# ESP8266.net
KiCad netlist of a schematic drawn in EasyEDA Pro
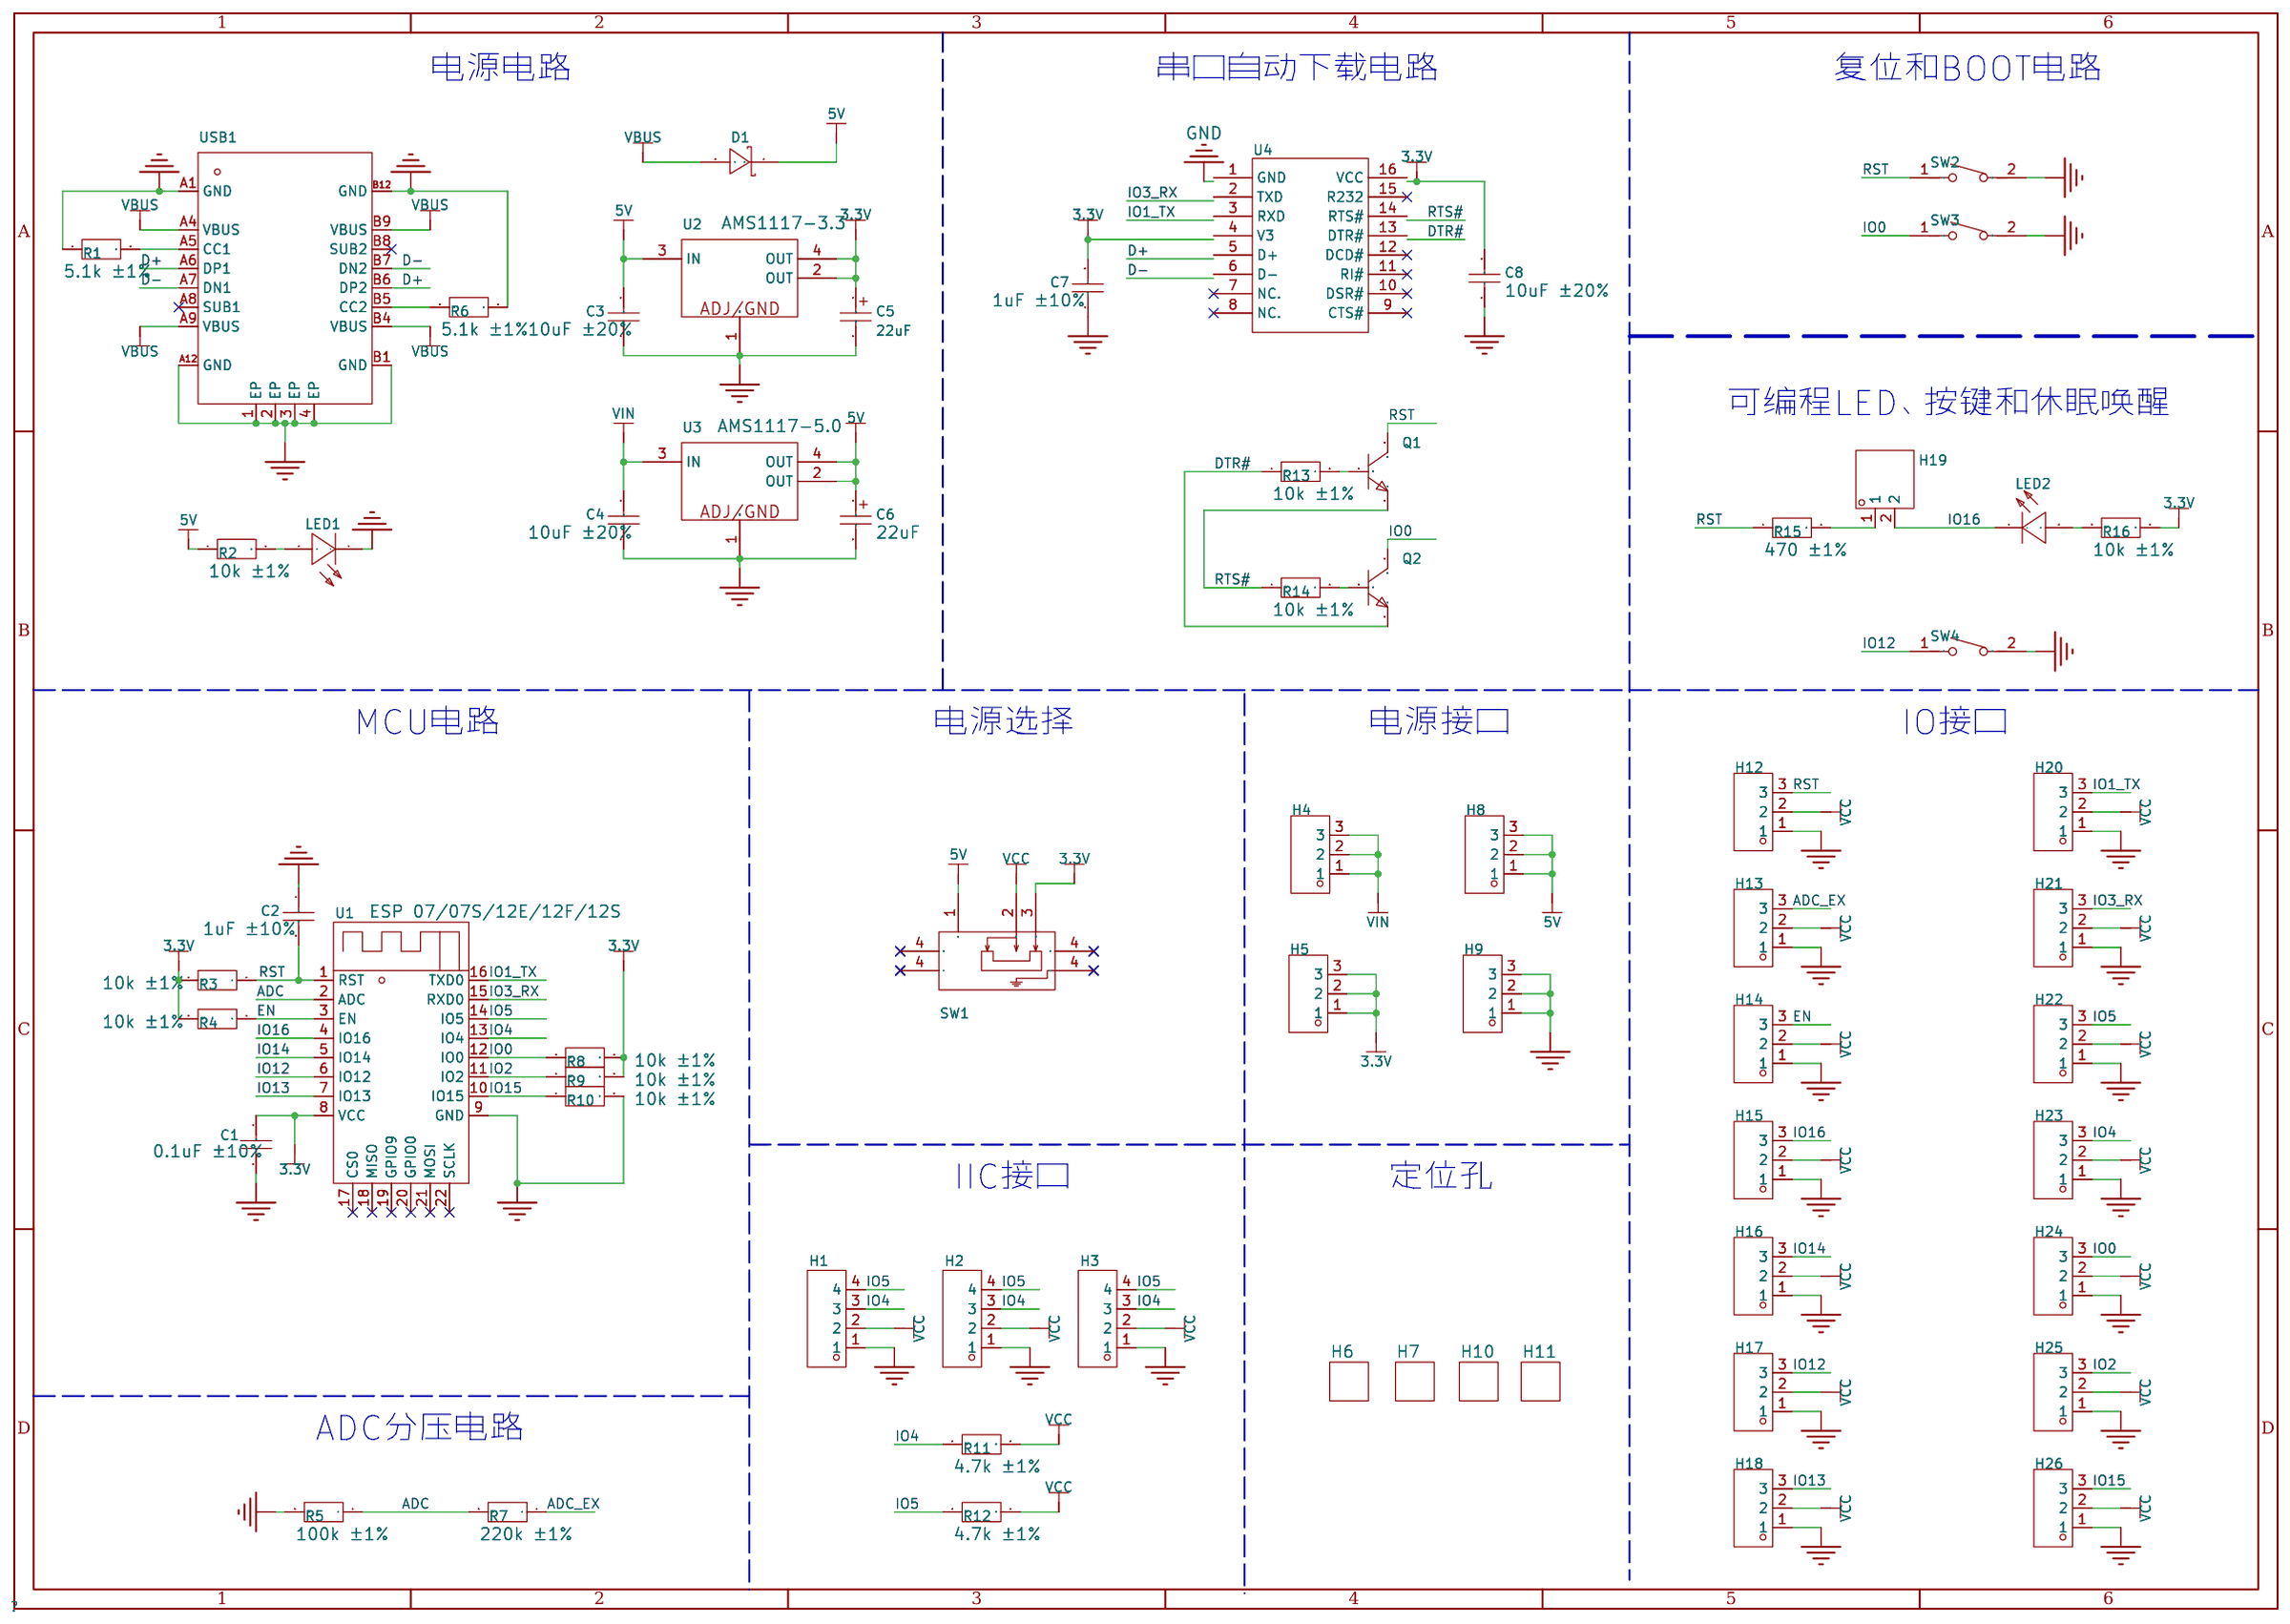
[diagram p0: schematic sheet]

(export (version "E")
  (design (tool "Eeschema 10.0.6"))
  (components
    (comp (ref "C1")
      (value "0.1uF ±10%")
      (footprint "easyedapro:C0603")
      (description "1uF ±10%")
      (libsource (lib "easyedapro") (part "C0603"))
    )
    (comp (ref "C2")
      (value "1uF ±10%")
      (footprint "easyedapro:C0603")
      (libsource (lib "easyedapro") (part "C0603"))
    )
    (comp (ref "C3")
      (value "10uF ±20%")
      (footprint "easyedapro:C0603")
      (description "10uF ±10%")
      (libsource (lib "easyedapro") (part "C0603"))
    )
    (comp (ref "C4")
      (value "10uF ±20%")
      (footprint "easyedapro:C0603")
      (description "10uF ±10%")
      (libsource (lib "easyedapro") (part "C0603"))
    )
    (comp (ref "C5")
      (value "22uF")
      (footprint "easyedapro:CAP-SMD_L3.5-W2.8-R-RD")
      (fields
        (field (name "Manufacturer Part") "CA45-B-25V-22uF-K")
        (field (name "Manufacturer") "CEC(振华新云)")
      )
      (libsource (lib "easyedapro") (part "CA45-B-25V-22UF"))
    )
    (comp (ref "C6")
      (value "22uF")
      (footprint "easyedapro:CAP-SMD_L3.5-W2.8-R-RD")
      (fields
        (field (name "Manufacturer Part") "CA45-B-25V-22uF-K")
        (field (name "Manufacturer") "CEC(振华新云)")
      )
      (libsource (lib "easyedapro") (part "CA45-B-25V-22UF"))
    )
    (comp (ref "C7")
      (value "1uF ±10%")
      (footprint "easyedapro:C0603")
      (libsource (lib "easyedapro") (part "C0603"))
    )
    (comp (ref "C8")
      (value "10uF ±20%")
      (footprint "easyedapro:C0603")
      (libsource (lib "easyedapro") (part "C0603"))
    )
    (comp (ref "D1")
      (value "SS24")
      (footprint "easyedapro:DO-214AC_L4.3-W2.7-LS5.3-RD")
      (description "直流反向耐压(Vr):40V;平均整流电流(Io):2A;正向压降(Vf):500mV@2A;")
      (fields (field (name "Manufacturer") "星海"))
      (libsource (lib "easyedapro") (part "SS24_C84028"))
    )
    (comp (ref "H1")
      (value "826629-4")
      (footprint "easyedapro:HDR-TH_4P-P2.54-V-M-1")
      (fields (field (name "Manufacturer") "TE Connectivity(美国泰科)"))
      (libsource (lib "easyedapro") (part "2.54-1*4P母"))
    )
    (comp (ref "H2")
      (value "826629-4")
      (footprint "easyedapro:HDR-TH_4P-P2.54-V-M-1")
      (fields (field (name "Manufacturer") "TE Connectivity(美国泰科)"))
      (libsource (lib "easyedapro") (part "2.54-1*4P母"))
    )
    (comp (ref "H3")
      (value "826629-4")
      (footprint "easyedapro:HDR-TH_4P-P2.54-V-M-1")
      (fields (field (name "Manufacturer") "TE Connectivity(美国泰科)"))
      (libsource (lib "easyedapro") (part "2.54-1*4P母"))
    )
    (comp (ref "H4")
      (value "2.54-1*3P针")
      (footprint "easyedapro:HDR-TH_3P-P2.54-V-M-1")
      (fields (field (name "Manufacturer") "BOOMELE(博穆精密)"))
      (libsource (lib "easyedapro") (part "PM254V-11-03-H85"))
    )
    (comp (ref "H5")
      (value "2.54-1*3P针")
      (footprint "easyedapro:HDR-TH_3P-P2.54-V-M-1")
      (fields (field (name "Manufacturer") "BOOMELE(博穆精密)"))
      (libsource (lib "easyedapro") (part "PM254V-11-03-H85"))
    )
    (comp (ref "H6")
      (value "Hole-3mm-JK 孔")
      (footprint "easyedapro:HOLE-3MM")
      (fields (field (name "Manufacturer Part") "Hole-3mm"))
      (libsource (lib "easyedapro") (part "Hole-3mm-JK 孔"))
    )
    (comp (ref "H7")
      (value "Hole-3mm-JK 孔")
      (footprint "easyedapro:HOLE-3MM")
      (fields (field (name "Manufacturer Part") "Hole-3mm"))
      (libsource (lib "easyedapro") (part "Hole-3mm-JK 孔"))
    )
    (comp (ref "H8")
      (value "2.54-1*3P针")
      (footprint "easyedapro:HDR-TH_3P-P2.54-V-M-1")
      (fields (field (name "Manufacturer") "BOOMELE(博穆精密)"))
      (libsource (lib "easyedapro") (part "PM254V-11-03-H85"))
    )
    (comp (ref "H9")
      (value "2.54-1*3P针")
      (footprint "easyedapro:HDR-TH_3P-P2.54-V-M-1")
      (fields (field (name "Manufacturer") "BOOMELE(博穆精密)"))
      (libsource (lib "easyedapro") (part "PM254V-11-03-H85"))
    )
    (comp (ref "H10")
      (value "Hole-3mm-JK 孔")
      (footprint "easyedapro:HOLE-3MM")
      (fields (field (name "Manufacturer Part") "Hole-3mm"))
      (libsource (lib "easyedapro") (part "Hole-3mm-JK 孔"))
    )
    (comp (ref "H11")
      (value "Hole-3mm-JK 孔")
      (footprint "easyedapro:HOLE-3MM")
      (fields (field (name "Manufacturer Part") "Hole-3mm"))
      (libsource (lib "easyedapro") (part "Hole-3mm-JK 孔"))
    )
    (comp (ref "H12")
      (value "2.54-1*3P针")
      (footprint "easyedapro:HDR-TH_3P-P2.54-V-M-1")
      (fields (field (name "Manufacturer") "BOOMELE(博穆精密)"))
      (libsource (lib "easyedapro") (part "PM254V-11-03-H85"))
    )
    (comp (ref "H13")
      (value "2.54-1*3P针")
      (footprint "easyedapro:HDR-TH_3P-P2.54-V-M-1")
      (fields (field (name "Manufacturer") "BOOMELE(博穆精密)"))
      (libsource (lib "easyedapro") (part "PM254V-11-03-H85"))
    )
    (comp (ref "H14")
      (value "2.54-1*3P针")
      (footprint "easyedapro:HDR-TH_3P-P2.54-V-M-1")
      (fields (field (name "Manufacturer") "BOOMELE(博穆精密)"))
      (libsource (lib "easyedapro") (part "PM254V-11-03-H85"))
    )
    (comp (ref "H15")
      (value "2.54-1*3P针")
      (footprint "easyedapro:HDR-TH_3P-P2.54-V-M-1")
      (fields (field (name "Manufacturer") "BOOMELE(博穆精密)"))
      (libsource (lib "easyedapro") (part "PM254V-11-03-H85"))
    )
    (comp (ref "H16")
      (value "2.54-1*3P针")
      (footprint "easyedapro:HDR-TH_3P-P2.54-V-M-1")
      (fields (field (name "Manufacturer") "BOOMELE(博穆精密)"))
      (libsource (lib "easyedapro") (part "PM254V-11-03-H85"))
    )
    (comp (ref "H17")
      (value "2.54-1*3P针")
      (footprint "easyedapro:HDR-TH_3P-P2.54-V-M-1")
      (fields (field (name "Manufacturer") "BOOMELE(博穆精密)"))
      (libsource (lib "easyedapro") (part "PM254V-11-03-H85"))
    )
    (comp (ref "H18")
      (value "2.54-1*3P针")
      (footprint "easyedapro:HDR-TH_3P-P2.54-V-M-1")
      (fields (field (name "Manufacturer") "BOOMELE(博穆精密)"))
      (libsource (lib "easyedapro") (part "PM254V-11-03-H85"))
    )
    (comp (ref "H19")
      (value "~")
      (footprint "easyedapro:HDR-TH_2P-P2.54-V-M-1")
      (libsource (lib "easyedapro") (part "210S-1*2P L=11.6MMGold-plated black"))
    )
    (comp (ref "H20")
      (value "2.54-1*3P针")
      (footprint "easyedapro:HDR-TH_3P-P2.54-V-M-1")
      (fields (field (name "Manufacturer") "BOOMELE(博穆精密)"))
      (libsource (lib "easyedapro") (part "PM254V-11-03-H85"))
    )
    (comp (ref "H21")
      (value "2.54-1*3P针")
      (footprint "easyedapro:HDR-TH_3P-P2.54-V-M-1")
      (fields (field (name "Manufacturer") "BOOMELE(博穆精密)"))
      (libsource (lib "easyedapro") (part "PM254V-11-03-H85"))
    )
    (comp (ref "H22")
      (value "2.54-1*3P针")
      (footprint "easyedapro:HDR-TH_3P-P2.54-V-M-1")
      (fields (field (name "Manufacturer") "BOOMELE(博穆精密)"))
      (libsource (lib "easyedapro") (part "PM254V-11-03-H85"))
    )
    (comp (ref "H23")
      (value "2.54-1*3P针")
      (footprint "easyedapro:HDR-TH_3P-P2.54-V-M-1")
      (fields (field (name "Manufacturer") "BOOMELE(博穆精密)"))
      (libsource (lib "easyedapro") (part "PM254V-11-03-H85"))
    )
    (comp (ref "H24")
      (value "2.54-1*3P针")
      (footprint "easyedapro:HDR-TH_3P-P2.54-V-M-1")
      (fields (field (name "Manufacturer") "BOOMELE(博穆精密)"))
      (libsource (lib "easyedapro") (part "PM254V-11-03-H85"))
    )
    (comp (ref "H25")
      (value "2.54-1*3P针")
      (footprint "easyedapro:HDR-TH_3P-P2.54-V-M-1")
      (fields (field (name "Manufacturer") "BOOMELE(博穆精密)"))
      (libsource (lib "easyedapro") (part "PM254V-11-03-H85"))
    )
    (comp (ref "H26")
      (value "2.54-1*3P针")
      (footprint "easyedapro:HDR-TH_3P-P2.54-V-M-1")
      (fields (field (name "Manufacturer") "BOOMELE(博穆精密)"))
      (libsource (lib "easyedapro") (part "PM254V-11-03-H85"))
    )
    (comp (ref "LED1")
      (value "~")
      (footprint "easyedapro:LED0805-RD")
      (description "LED 0805;")
      (fields (field (name "Manufacturer") "国星光电"))
      (libsource (lib "easyedapro") (part "FC-2012WBY-460G"))
    )
    (comp (ref "LED2")
      (value "~")
      (footprint "easyedapro:LED0805-RD")
      (description "LED 0805;")
      (fields (field (name "Manufacturer") "国星光电"))
      (libsource (lib "easyedapro") (part "FC-2012WBY-460G"))
    )
    (comp (ref "Q1")
      (value "S8050")
      (footprint "easyedapro:SOT-23-3_L2.9-W1.3-P1.90-LS2.4-BR")
      (description "NPN 25V 500mA 120-400 SOT-23")
      (fields (field (name "Manufacturer") "Doeshare(德芯)"))
      (libsource (lib "easyedapro") (part "S8050_C2931719"))
    )
    (comp (ref "Q2")
      (value "S8050")
      (footprint "easyedapro:SOT-23-3_L2.9-W1.3-P1.90-LS2.4-BR")
      (description "NPN 25V 500mA 120-400 SOT-23")
      (fields (field (name "Manufacturer") "Doeshare(德芯)"))
      (libsource (lib "easyedapro") (part "S8050_C2931719"))
    )
    (comp (ref "R1")
      (value "5.1k ±1%")
      (footprint "easyedapro:R0603")
      (description "10k ±1%")
      (fields (field (name "Manufacturer Part") "CR0603FA4R30G") (field (name "Manufacturer") "LIZ(丽智电子)"))
      (libsource (lib "easyedapro") (part "CR0603FA4R30G"))
    )
    (comp (ref "R2")
      (value "10k ±1%")
      (footprint "easyedapro:R0603")
      (fields (field (name "Manufacturer Part") "CR0603FA4R30G") (field (name "Manufacturer") "LIZ(丽智电子)"))
      (libsource (lib "easyedapro") (part "CR0603FA4R30G"))
    )
    (comp (ref "R3")
      (value "10k ±1%")
      (footprint "easyedapro:R0603")
      (fields (field (name "Manufacturer Part") "CR0603FA4R30G") (field (name "Manufacturer") "LIZ(丽智电子)"))
      (libsource (lib "easyedapro") (part "CR0603FA4R30G"))
    )
    (comp (ref "R4")
      (value "10k ±1%")
      (footprint "easyedapro:R0603")
      (fields (field (name "Manufacturer Part") "CR0603FA4R30G") (field (name "Manufacturer") "LIZ(丽智电子)"))
      (libsource (lib "easyedapro") (part "CR0603FA4R30G"))
    )
    (comp (ref "R5")
      (value "100k ±1%")
      (footprint "easyedapro:R0603")
      (description "10k ±1%")
      (fields (field (name "Manufacturer Part") "CR0603FA4R30G") (field (name "Manufacturer") "LIZ(丽智电子)"))
      (libsource (lib "easyedapro") (part "CR0603FA4R30G"))
    )
    (comp (ref "R6")
      (value "5.1k ±1%")
      (footprint "easyedapro:R0603")
      (description "10k ±1%")
      (fields (field (name "Manufacturer Part") "CR0603FA4R30G") (field (name "Manufacturer") "LIZ(丽智电子)"))
      (libsource (lib "easyedapro") (part "CR0603FA4R30G"))
    )
    (comp (ref "R7")
      (value "220k ±1%")
      (footprint "easyedapro:R0603")
      (description "10k ±1%")
      (fields (field (name "Manufacturer Part") "CR0603FA4R30G") (field (name "Manufacturer") "LIZ(丽智电子)"))
      (libsource (lib "easyedapro") (part "CR0603FA4R30G"))
    )
    (comp (ref "R8")
      (value "10k ±1%")
      (footprint "easyedapro:R0603")
      (fields (field (name "Manufacturer Part") "CR0603FA4R30G") (field (name "Manufacturer") "LIZ(丽智电子)"))
      (libsource (lib "easyedapro") (part "CR0603FA4R30G"))
    )
    (comp (ref "R9")
      (value "10k ±1%")
      (footprint "easyedapro:R0603")
      (fields (field (name "Manufacturer Part") "CR0603FA4R30G") (field (name "Manufacturer") "LIZ(丽智电子)"))
      (libsource (lib "easyedapro") (part "CR0603FA4R30G"))
    )
    (comp (ref "R10")
      (value "10k ±1%")
      (footprint "easyedapro:R0603")
      (fields (field (name "Manufacturer Part") "CR0603FA4R30G") (field (name "Manufacturer") "LIZ(丽智电子)"))
      (libsource (lib "easyedapro") (part "CR0603FA4R30G"))
    )
    (comp (ref "R11")
      (value "4.7k ±1%")
      (footprint "easyedapro:R0603")
      (description "10k ±1%")
      (fields (field (name "Manufacturer Part") "CR0603FA4R30G") (field (name "Manufacturer") "LIZ(丽智电子)"))
      (libsource (lib "easyedapro") (part "CR0603FA4R30G"))
    )
    (comp (ref "R12")
      (value "4.7k ±1%")
      (footprint "easyedapro:R0603")
      (description "10k ±1%")
      (fields (field (name "Manufacturer Part") "CR0603FA4R30G") (field (name "Manufacturer") "LIZ(丽智电子)"))
      (libsource (lib "easyedapro") (part "CR0603FA4R30G"))
    )
    (comp (ref "R13")
      (value "10k ±1%")
      (footprint "easyedapro:R0603")
      (fields (field (name "Manufacturer Part") "CR0603FA4R30G") (field (name "Manufacturer") "LIZ(丽智电子)"))
      (libsource (lib "easyedapro") (part "CR0603FA4R30G"))
    )
    (comp (ref "R14")
      (value "10k ±1%")
      (footprint "easyedapro:R0603")
      (fields (field (name "Manufacturer Part") "CR0603FA4R30G") (field (name "Manufacturer") "LIZ(丽智电子)"))
      (libsource (lib "easyedapro") (part "CR0603FA4R30G"))
    )
    (comp (ref "R15")
      (value "470 ±1%")
      (footprint "easyedapro:R0603")
      (description "10k ±1%")
      (fields (field (name "Manufacturer Part") "CR0603FA4R30G") (field (name "Manufacturer") "LIZ(丽智电子)"))
      (libsource (lib "easyedapro") (part "CR0603FA4R30G"))
    )
    (comp (ref "R16")
      (value "10k ±1%")
      (footprint "easyedapro:R0603")
      (fields (field (name "Manufacturer Part") "CR0603FA4R30G") (field (name "Manufacturer") "LIZ(丽智电子)"))
      (libsource (lib "easyedapro") (part "CR0603FA4R30G"))
    )
    (comp (ref "SW1")
      (value "MSK12C02")
      (footprint "easyedapro:SW-TH_MSK12C02")
      (fields (field (name "Manufacturer") "SHOU HAN(首韩)"))
      (libsource (lib "easyedapro") (part "MSK12C02"))
    )
    (comp (ref "SW2")
      (value "TS-KG88C-ACT25F")
      (footprint "easyedapro:KEY-SMD_L4.0-W2.9-LS4.8")
      (fields (field (name "Manufacturer") "HANBO(汉博)"))
      (libsource (lib "easyedapro") (part "TS-KG88C-ACT25F"))
    )
    (comp (ref "SW3")
      (value "TS-KG88C-ACT25F")
      (footprint "easyedapro:KEY-SMD_L4.0-W2.9-LS4.8")
      (fields (field (name "Manufacturer") "HANBO(汉博)"))
      (libsource (lib "easyedapro") (part "TS-KG88C-ACT25F"))
    )
    (comp (ref "SW4")
      (value "TS-KG88C-ACT25F")
      (footprint "easyedapro:KEY-SMD_L4.0-W2.9-LS4.8")
      (fields (field (name "Manufacturer") "HANBO(汉博)"))
      (libsource (lib "easyedapro") (part "TS-KG88C-ACT25F"))
    )
    (comp (ref "U1")
      (value "ESP 07/07S/12E/12F/12S")
      (footprint "easyedapro:WIFIM-SMD_22P-L24.0-W16.0-P2.00")
      (fields
        (field (name "Manufacturer Part") "WT8266-S5 ESP-12F")
        (field (name "Manufacturer") "Wireless-tag(启明云端)")
      )
      (libsource (lib "easyedapro") (part "WT8266-S5 ESP-12F"))
    )
    (comp (ref "U2")
      (value "AMS1117-3.3")
      (footprint "easyedapro:SOT-223-3_L6.4-W3.5-P2.30-LS7.0-BR")
      (fields (field (name "Manufacturer") "国芯佳品"))
      (libsource (lib "easyedapro") (part "AMS1117-3.3_C2992570"))
    )
    (comp (ref "U3")
      (value "AMS1117-5.0")
      (footprint "easyedapro:SOT-223-3_L6.4-W3.5-P2.30-LS7.0-BR")
      (fields (field (name "Manufacturer Part") "AMS1117-3.3") (field (name "Manufacturer") "国芯佳品"))
      (libsource (lib "easyedapro") (part "AMS1117-3.3_C2992570"))
    )
    (comp (ref "U4")
      (value "CH340C")
      (footprint "easyedapro:SOP-16_L10.0-W3.9-P1.27-LS6.0-BL")
      (description "类型:Transceiver;协议类别:USB 2.0;驱动器/接收器数:-;数据速率:2Mbps;")
      (fields (field (name "Manufacturer") "WCH(南京沁恒)"))
      (libsource (lib "easyedapro") (part "CH340C"))
    )
    (comp (ref "USB1")
      (value "KH-TYPE-C-16P")
      (footprint "easyedapro:USB-C-SMD_KH-TYPE-C-16P")
      (description "连接器类型:Type-C;标准:-;公母:母座;触点数量:16;端口数量:1;安装方式:卧贴;额定电流 - 电源:3A;工作温度范围:-40~+85;")
      (fields (field (name "Manufacturer") "kinghelm(金航标)"))
      (libsource (lib "easyedapro") (part "KH-TYPE-C-16P"))
    )
  )
  (nets
    (net (code "1") (name "/ADC") (class "Default")
      (node (ref "R5") (pin "1") (pinfunction "1_1") (pintype "input"))
      (node (ref "R7") (pin "2") (pinfunction "2_2") (pintype "input"))
      (node (ref "U1") (pin "2") (pinfunction "ADC_2") (pintype "input"))
    )
    (net (code "2") (name "/ADC_EX") (class "Default")
      (node (ref "H13") (pin "3") (pinfunction "3_3") (pintype "input"))
      (node (ref "R7") (pin "1") (pinfunction "1_1") (pintype "input"))
    )
    (net (code "3") (name "/D+") (class "Default")
      (node (ref "USB1") (pin "A6") (pinfunction "DP1_A6") (pintype "input"))
      (node (ref "USB1") (pin "B6") (pinfunction "DP2_B6") (pintype "input"))
    )
    (net (code "4") (name "/D-") (class "Default")
      (node (ref "USB1") (pin "A7") (pinfunction "DN1_A7") (pintype "input"))
      (node (ref "USB1") (pin "B7") (pinfunction "DN2_B7") (pintype "input"))
    )
    (net (code "5") (name "/DTR#") (class "Default")
      (node (ref "Q2") (pin "2") (pinfunction "E_2") (pintype "input"))
      (node (ref "R13") (pin "1") (pinfunction "1_1") (pintype "input"))
    )
    (net (code "6") (name "/EN") (class "Default")
      (node (ref "H14") (pin "3") (pinfunction "3_3") (pintype "input"))
      (node (ref "R4") (pin "1") (pinfunction "1_1") (pintype "input"))
      (node (ref "U1") (pin "3") (pinfunction "EN_3") (pintype "input"))
    )
    (net (code "7") (name "/IO0") (class "Default")
      (node (ref "H24") (pin "3") (pinfunction "3_3") (pintype "input"))
      (node (ref "Q2") (pin "3") (pinfunction "C_3") (pintype "input"))
      (node (ref "R8") (pin "1") (pinfunction "1_1") (pintype "input"))
      (node (ref "SW3") (pin "1") (pinfunction "1_1") (pintype "input"))
      (node (ref "U1") (pin "12") (pinfunction "IO0_12") (pintype "input"))
    )
    (net (code "8") (name "/IO1_TX") (class "Default")
      (node (ref "H20") (pin "3") (pinfunction "3_3") (pintype "input"))
      (node (ref "U1") (pin "16") (pinfunction "TXD0_16") (pintype "input"))
    )
    (net (code "9") (name "/IO2") (class "Default")
      (node (ref "H25") (pin "3") (pinfunction "3_3") (pintype "input"))
      (node (ref "R9") (pin "1") (pinfunction "1_1") (pintype "input"))
      (node (ref "U1") (pin "11") (pinfunction "IO2_11") (pintype "input"))
    )
    (net (code "10") (name "/IO3_RX") (class "Default")
      (node (ref "H21") (pin "3") (pinfunction "3_3") (pintype "input"))
      (node (ref "U1") (pin "15") (pinfunction "RXD0_15") (pintype "input"))
    )
    (net (code "11") (name "/IO4") (class "Default")
      (node (ref "H1") (pin "3") (pinfunction "3_3") (pintype "input"))
      (node (ref "H2") (pin "3") (pinfunction "3_3") (pintype "input"))
      (node (ref "H23") (pin "3") (pinfunction "3_3") (pintype "input"))
      (node (ref "H3") (pin "3") (pinfunction "3_3") (pintype "input"))
      (node (ref "R11") (pin "2") (pinfunction "2_2") (pintype "input"))
      (node (ref "U1") (pin "13") (pinfunction "IO4_13") (pintype "input"))
    )
    (net (code "12") (name "/IO5") (class "Default")
      (node (ref "H1") (pin "4") (pinfunction "4_4") (pintype "input"))
      (node (ref "H2") (pin "4") (pinfunction "4_4") (pintype "input"))
      (node (ref "H22") (pin "3") (pinfunction "3_3") (pintype "input"))
      (node (ref "H3") (pin "4") (pinfunction "4_4") (pintype "input"))
      (node (ref "R12") (pin "2") (pinfunction "2_2") (pintype "input"))
      (node (ref "U1") (pin "14") (pinfunction "IO5_14") (pintype "input"))
    )
    (net (code "13") (name "/IO12") (class "Default")
      (node (ref "H17") (pin "3") (pinfunction "3_3") (pintype "input"))
      (node (ref "SW4") (pin "1") (pinfunction "1_1") (pintype "input"))
      (node (ref "U1") (pin "6") (pinfunction "IO12_6") (pintype "input"))
    )
    (net (code "14") (name "/IO13") (class "Default")
      (node (ref "H18") (pin "3") (pinfunction "3_3") (pintype "input"))
      (node (ref "U1") (pin "7") (pinfunction "IO13_7") (pintype "input"))
    )
    (net (code "15") (name "/IO14") (class "Default")
      (node (ref "H16") (pin "3") (pinfunction "3_3") (pintype "input"))
      (node (ref "U1") (pin "5") (pinfunction "IO14_5") (pintype "input"))
    )
    (net (code "16") (name "/IO15") (class "Default")
      (node (ref "H26") (pin "3") (pinfunction "3_3") (pintype "input"))
      (node (ref "R10") (pin "1") (pinfunction "1_1") (pintype "input"))
      (node (ref "U1") (pin "10") (pinfunction "IO15_10") (pintype "input"))
    )
    (net (code "17") (name "/IO16") (class "Default")
      (node (ref "H15") (pin "3") (pinfunction "3_3") (pintype "input"))
      (node (ref "H19") (pin "2") (pinfunction "2_2") (pintype "input"))
      (node (ref "LED2") (pin "1") (pinfunction "-_1") (pintype "input"))
      (node (ref "U1") (pin "4") (pinfunction "IO16_4") (pintype "input"))
    )
    (net (code "18") (name "/RST") (class "Default")
      (node (ref "C2") (pin "2") (pinfunction "2_2") (pintype "unspecified"))
      (node (ref "H12") (pin "3") (pinfunction "3_3") (pintype "input"))
      (node (ref "Q1") (pin "3") (pinfunction "C_3") (pintype "input"))
      (node (ref "R15") (pin "1") (pinfunction "1_1") (pintype "input"))
      (node (ref "R3") (pin "1") (pinfunction "1_1") (pintype "input"))
      (node (ref "SW2") (pin "1") (pinfunction "1_1") (pintype "input"))
      (node (ref "U1") (pin "1") (pinfunction "RST_1") (pintype "input"))
    )
    (net (code "19") (name "/RTS#") (class "Default")
      (node (ref "Q1") (pin "2") (pinfunction "E_2") (pintype "input"))
      (node (ref "R14") (pin "1") (pinfunction "1_1") (pintype "input"))
    )
    (net (code "20") (name "3.3V") (class "Default")
      (node (ref "C1") (pin "1") (pinfunction "1_1") (pintype "unspecified"))
      (node (ref "C5") (pin "1") (pinfunction "1_1") (pintype "input"))
      (node (ref "C7") (pin "2") (pinfunction "2_2") (pintype "unspecified"))
      (node (ref "C8") (pin "1") (pinfunction "1_1") (pintype "unspecified"))
      (node (ref "H5") (pin "1") (pinfunction "1_1") (pintype "input"))
      (node (ref "H5") (pin "2") (pinfunction "2_2") (pintype "input"))
      (node (ref "H5") (pin "3") (pinfunction "3_3") (pintype "input"))
      (node (ref "R16") (pin "2") (pinfunction "2_2") (pintype "input"))
      (node (ref "R3") (pin "2") (pinfunction "2_2") (pintype "input"))
      (node (ref "R4") (pin "2") (pinfunction "2_2") (pintype "input"))
      (node (ref "R8") (pin "2") (pinfunction "2_2") (pintype "input"))
      (node (ref "R9") (pin "2") (pinfunction "2_2") (pintype "input"))
      (node (ref "SW1") (pin "3") (pinfunction "3_3") (pintype "input"))
      (node (ref "U1") (pin "8") (pinfunction "VCC_8") (pintype "input"))
      (node (ref "U2") (pin "2") (pinfunction "OUT_2") (pintype "input"))
      (node (ref "U2") (pin "4") (pinfunction "OUT_4") (pintype "input"))
    )
    (net (code "21") (name "5V") (class "Default")
      (node (ref "C3") (pin "2") (pinfunction "2_2") (pintype "unspecified"))
      (node (ref "C6") (pin "1") (pinfunction "1_1") (pintype "input"))
      (node (ref "D1") (pin "1") (pinfunction "K_1") (pintype "input"))
      (node (ref "H8") (pin "1") (pinfunction "1_1") (pintype "input"))
      (node (ref "H8") (pin "2") (pinfunction "2_2") (pintype "input"))
      (node (ref "H8") (pin "3") (pinfunction "3_3") (pintype "input"))
      (node (ref "R2") (pin "1") (pinfunction "1_1") (pintype "input"))
      (node (ref "SW1") (pin "1") (pinfunction "1_1") (pintype "input"))
      (node (ref "U2") (pin "3") (pinfunction "IN_3") (pintype "input"))
      (node (ref "U3") (pin "2") (pinfunction "OUT_2") (pintype "input"))
      (node (ref "U3") (pin "4") (pinfunction "OUT_4") (pintype "input"))
    )
    (net (code "22") (name "GND") (class "Default")
      (node (ref "C1") (pin "2") (pinfunction "2_2") (pintype "unspecified"))
      (node (ref "C2") (pin "1") (pinfunction "1_1") (pintype "unspecified"))
      (node (ref "C3") (pin "1") (pinfunction "1_1") (pintype "unspecified"))
      (node (ref "C4") (pin "1") (pinfunction "1_1") (pintype "unspecified"))
      (node (ref "C5") (pin "2") (pinfunction "2_2") (pintype "input"))
      (node (ref "C6") (pin "2") (pinfunction "2_2") (pintype "input"))
      (node (ref "C7") (pin "1") (pinfunction "1_1") (pintype "unspecified"))
      (node (ref "C8") (pin "2") (pinfunction "2_2") (pintype "unspecified"))
      (node (ref "H1") (pin "1") (pinfunction "1_1") (pintype "input"))
      (node (ref "H12") (pin "1") (pinfunction "1_1") (pintype "input"))
      (node (ref "H13") (pin "1") (pinfunction "1_1") (pintype "input"))
      (node (ref "H14") (pin "1") (pinfunction "1_1") (pintype "input"))
      (node (ref "H15") (pin "1") (pinfunction "1_1") (pintype "input"))
      (node (ref "H16") (pin "1") (pinfunction "1_1") (pintype "input"))
      (node (ref "H17") (pin "1") (pinfunction "1_1") (pintype "input"))
      (node (ref "H18") (pin "1") (pinfunction "1_1") (pintype "input"))
      (node (ref "H2") (pin "1") (pinfunction "1_1") (pintype "input"))
      (node (ref "H20") (pin "1") (pinfunction "1_1") (pintype "input"))
      (node (ref "H21") (pin "1") (pinfunction "1_1") (pintype "input"))
      (node (ref "H22") (pin "1") (pinfunction "1_1") (pintype "input"))
      (node (ref "H23") (pin "1") (pinfunction "1_1") (pintype "input"))
      (node (ref "H24") (pin "1") (pinfunction "1_1") (pintype "input"))
      (node (ref "H25") (pin "1") (pinfunction "1_1") (pintype "input"))
      (node (ref "H26") (pin "1") (pinfunction "1_1") (pintype "input"))
      (node (ref "H3") (pin "1") (pinfunction "1_1") (pintype "input"))
      (node (ref "H9") (pin "1") (pinfunction "1_1") (pintype "input"))
      (node (ref "H9") (pin "2") (pinfunction "2_2") (pintype "input"))
      (node (ref "H9") (pin "3") (pinfunction "3_3") (pintype "input"))
      (node (ref "LED1") (pin "1") (pinfunction "-_1") (pintype "input"))
      (node (ref "R1") (pin "1") (pinfunction "1_1") (pintype "input"))
      (node (ref "R10") (pin "2") (pinfunction "2_2") (pintype "input"))
      (node (ref "R5") (pin "2") (pinfunction "2_2") (pintype "input"))
      (node (ref "R6") (pin "2") (pinfunction "2_2") (pintype "input"))
      (node (ref "SW2") (pin "2") (pinfunction "2_2") (pintype "input"))
      (node (ref "SW3") (pin "2") (pinfunction "2_2") (pintype "input"))
      (node (ref "SW4") (pin "2") (pinfunction "2_2") (pintype "input"))
      (node (ref "U1") (pin "9") (pinfunction "GND_9") (pintype "input"))
      (node (ref "U2") (pin "1") (pinfunction "ADJ/GND_1") (pintype "input"))
      (node (ref "U3") (pin "1") (pinfunction "ADJ/GND_1") (pintype "input"))
      (node (ref "USB1") (pin "1") (pinfunction "EP_1") (pintype "input"))
      (node (ref "USB1") (pin "2") (pinfunction "EP_2") (pintype "input"))
      (node (ref "USB1") (pin "3") (pinfunction "EP_3") (pintype "input"))
      (node (ref "USB1") (pin "4") (pinfunction "EP_4") (pintype "input"))
      (node (ref "USB1") (pin "A1") (pinfunction "GND_A1") (pintype "input"))
      (node (ref "USB1") (pin "A12") (pinfunction "GND_A12") (pintype "input"))
      (node (ref "USB1") (pin "B1") (pinfunction "GND_B1") (pintype "input"))
      (node (ref "USB1") (pin "B12") (pinfunction "GND_B12") (pintype "input"))
    )
    (net (code "23") (name "Net-(H19-Pad1)") (class "Default")
      (node (ref "H19") (pin "1") (pinfunction "1_1") (pintype "input"))
      (node (ref "R15") (pin "2") (pinfunction "2_2") (pintype "input"))
    )
    (net (code "24") (name "Net-(LED1-+)") (class "Default")
      (node (ref "LED1") (pin "2") (pinfunction "+_2") (pintype "input"))
      (node (ref "R2") (pin "2") (pinfunction "2_2") (pintype "input"))
    )
    (net (code "25") (name "Net-(LED2-+)") (class "Default")
      (node (ref "LED2") (pin "2") (pinfunction "+_2") (pintype "input"))
      (node (ref "R16") (pin "1") (pinfunction "1_1") (pintype "input"))
    )
    (net (code "26") (name "Net-(Q1-B)") (class "Default")
      (node (ref "Q1") (pin "1") (pinfunction "B_1") (pintype "input"))
      (node (ref "R13") (pin "2") (pinfunction "2_2") (pintype "input"))
    )
    (net (code "27") (name "Net-(Q2-B)") (class "Default")
      (node (ref "Q2") (pin "1") (pinfunction "B_1") (pintype "input"))
      (node (ref "R14") (pin "2") (pinfunction "2_2") (pintype "input"))
    )
    (net (code "28") (name "Net-(USB1-CC1)") (class "Default")
      (node (ref "R1") (pin "2") (pinfunction "2_2") (pintype "input"))
      (node (ref "USB1") (pin "A5") (pinfunction "CC1_A5") (pintype "input"))
    )
    (net (code "29") (name "Net-(USB1-CC2)") (class "Default")
      (node (ref "R6") (pin "1") (pinfunction "1_1") (pintype "input"))
      (node (ref "USB1") (pin "B5") (pinfunction "CC2_B5") (pintype "input"))
    )
    (net (code "30") (name "VBUS") (class "Default")
      (node (ref "D1") (pin "2") (pinfunction "A_2") (pintype "input"))
      (node (ref "USB1") (pin "A4") (pinfunction "VBUS_A4") (pintype "input"))
      (node (ref "USB1") (pin "A9") (pinfunction "VBUS_A9") (pintype "input"))
      (node (ref "USB1") (pin "B4") (pinfunction "VBUS_B4") (pintype "input"))
      (node (ref "USB1") (pin "B9") (pinfunction "VBUS_B9") (pintype "input"))
    )
    (net (code "31") (name "VCC") (class "Default")
      (node (ref "H1") (pin "2") (pinfunction "2_2") (pintype "input"))
      (node (ref "H12") (pin "2") (pinfunction "2_2") (pintype "input"))
      (node (ref "H13") (pin "2") (pinfunction "2_2") (pintype "input"))
      (node (ref "H14") (pin "2") (pinfunction "2_2") (pintype "input"))
      (node (ref "H15") (pin "2") (pinfunction "2_2") (pintype "input"))
      (node (ref "H16") (pin "2") (pinfunction "2_2") (pintype "input"))
      (node (ref "H17") (pin "2") (pinfunction "2_2") (pintype "input"))
      (node (ref "H18") (pin "2") (pinfunction "2_2") (pintype "input"))
      (node (ref "H2") (pin "2") (pinfunction "2_2") (pintype "input"))
      (node (ref "H20") (pin "2") (pinfunction "2_2") (pintype "input"))
      (node (ref "H21") (pin "2") (pinfunction "2_2") (pintype "input"))
      (node (ref "H22") (pin "2") (pinfunction "2_2") (pintype "input"))
      (node (ref "H23") (pin "2") (pinfunction "2_2") (pintype "input"))
      (node (ref "H24") (pin "2") (pinfunction "2_2") (pintype "input"))
      (node (ref "H25") (pin "2") (pinfunction "2_2") (pintype "input"))
      (node (ref "H26") (pin "2") (pinfunction "2_2") (pintype "input"))
      (node (ref "H3") (pin "2") (pinfunction "2_2") (pintype "input"))
      (node (ref "R11") (pin "1") (pinfunction "1_1") (pintype "input"))
      (node (ref "R12") (pin "1") (pinfunction "1_1") (pintype "input"))
      (node (ref "SW1") (pin "2") (pinfunction "2_2") (pintype "input"))
    )
    (net (code "32") (name "VIN") (class "Default")
      (node (ref "C4") (pin "2") (pinfunction "2_2") (pintype "unspecified"))
      (node (ref "H4") (pin "1") (pinfunction "1_1") (pintype "input"))
      (node (ref "H4") (pin "2") (pinfunction "2_2") (pintype "input"))
      (node (ref "H4") (pin "3") (pinfunction "3_3") (pintype "input"))
      (node (ref "U3") (pin "3") (pinfunction "IN_3") (pintype "input"))
    )
    (net (code "33") (name "unconnected-(SW1-Pad4)") (class "Default")
      (node (ref "SW1") (pin "4") (pinfunction "4_4") (pintype "input+no_connect"))
    )
    (net (code "34") (name "unconnected-(SW1-Pad4)_1") (class "Default")
      (node (ref "SW1") (pin "4") (pinfunction "4_4") (pintype "input+no_connect"))
    )
    (net (code "35") (name "unconnected-(SW1-Pad4)_2") (class "Default")
      (node (ref "SW1") (pin "4") (pinfunction "4_4") (pintype "input+no_connect"))
    )
    (net (code "36") (name "unconnected-(SW1-Pad4)_3") (class "Default")
      (node (ref "SW1") (pin "4") (pinfunction "4_4") (pintype "input+no_connect"))
    )
    (net (code "37") (name "unconnected-(U1-CS0-Pad17)") (class "Default")
      (node (ref "U1") (pin "17") (pinfunction "CS0_17") (pintype "input+no_connect"))
    )
    (net (code "38") (name "unconnected-(U1-GPIO0-Pad20)") (class "Default")
      (node (ref "U1") (pin "20") (pinfunction "GPIO0_20") (pintype "input+no_connect"))
    )
    (net (code "39") (name "unconnected-(U1-GPIO9-Pad19)") (class "Default")
      (node (ref "U1") (pin "19") (pinfunction "GPIO9_19") (pintype "input+no_connect"))
    )
    (net (code "40") (name "unconnected-(U1-MISO-Pad18)") (class "Default")
      (node (ref "U1") (pin "18") (pinfunction "MISO_18") (pintype "input+no_connect"))
    )
    (net (code "41") (name "unconnected-(U1-MOSI-Pad21)") (class "Default")
      (node (ref "U1") (pin "21") (pinfunction "MOSI_21") (pintype "input+no_connect"))
    )
    (net (code "42") (name "unconnected-(U1-SCLK-Pad22)") (class "Default")
      (node (ref "U1") (pin "22") (pinfunction "SCLK_22") (pintype "input+no_connect"))
    )
    (net (code "43") (name "unconnected-(U4-CTS#-Pad9)") (class "Default")
      (node (ref "U4") (pin "9") (pinfunction "CTS#_9") (pintype "input+no_connect"))
    )
    (net (code "44") (name "unconnected-(U4-D+-Pad5)") (class "Default")
      (node (ref "U4") (pin "5") (pinfunction "D+_5") (pintype "input"))
    )
    (net (code "45") (name "unconnected-(U4-D--Pad6)") (class "Default")
      (node (ref "U4") (pin "6") (pinfunction "D-_6") (pintype "input"))
    )
    (net (code "46") (name "unconnected-(U4-DCD#-Pad12)") (class "Default")
      (node (ref "U4") (pin "12") (pinfunction "DCD#_12") (pintype "input+no_connect"))
    )
    (net (code "47") (name "unconnected-(U4-DSR#-Pad10)") (class "Default")
      (node (ref "U4") (pin "10") (pinfunction "DSR#_10") (pintype "input+no_connect"))
    )
    (net (code "48") (name "unconnected-(U4-DTR#-Pad13)") (class "Default")
      (node (ref "U4") (pin "13") (pinfunction "DTR#_13") (pintype "input"))
    )
    (net (code "49") (name "unconnected-(U4-GND-Pad1)") (class "Default")
      (node (ref "U4") (pin "1") (pinfunction "GND_1") (pintype "input"))
    )
    (net (code "50") (name "unconnected-(U4-NC.-Pad7)") (class "Default")
      (node (ref "U4") (pin "7") (pinfunction "NC._7") (pintype "input+no_connect"))
    )
    (net (code "51") (name "unconnected-(U4-NC.-Pad8)") (class "Default")
      (node (ref "U4") (pin "8") (pinfunction "NC._8") (pintype "input+no_connect"))
    )
    (net (code "52") (name "unconnected-(U4-R232-Pad15)") (class "Default")
      (node (ref "U4") (pin "15") (pinfunction "R232_15") (pintype "input+no_connect"))
    )
    (net (code "53") (name "unconnected-(U4-RI#-Pad11)") (class "Default")
      (node (ref "U4") (pin "11") (pinfunction "RI#_11") (pintype "input+no_connect"))
    )
    (net (code "54") (name "unconnected-(U4-RTS#-Pad14)") (class "Default")
      (node (ref "U4") (pin "14") (pinfunction "RTS#_14") (pintype "input"))
    )
    (net (code "55") (name "unconnected-(U4-RXD-Pad3)") (class "Default")
      (node (ref "U4") (pin "3") (pinfunction "RXD_3") (pintype "input"))
    )
    (net (code "56") (name "unconnected-(U4-TXD-Pad2)") (class "Default")
      (node (ref "U4") (pin "2") (pinfunction "TXD_2") (pintype "input"))
    )
    (net (code "57") (name "unconnected-(U4-V3-Pad4)") (class "Default")
      (node (ref "U4") (pin "4") (pinfunction "V3_4") (pintype "input"))
    )
    (net (code "58") (name "unconnected-(U4-VCC-Pad16)") (class "Default")
      (node (ref "U4") (pin "16") (pinfunction "VCC_16") (pintype "input"))
    )
    (net (code "59") (name "unconnected-(USB1-SUB1-PadA8)") (class "Default")
      (node (ref "USB1") (pin "A8") (pinfunction "SUB1_A8") (pintype "input+no_connect"))
    )
    (net (code "60") (name "unconnected-(USB1-SUB2-PadB8)") (class "Default")
      (node (ref "USB1") (pin "B8") (pinfunction "SUB2_B8") (pintype "input+no_connect"))
    )
  )
)
